# reefpi_pico_analog_out.net
KiCad netlist of a schematic drawn in Altium Designer
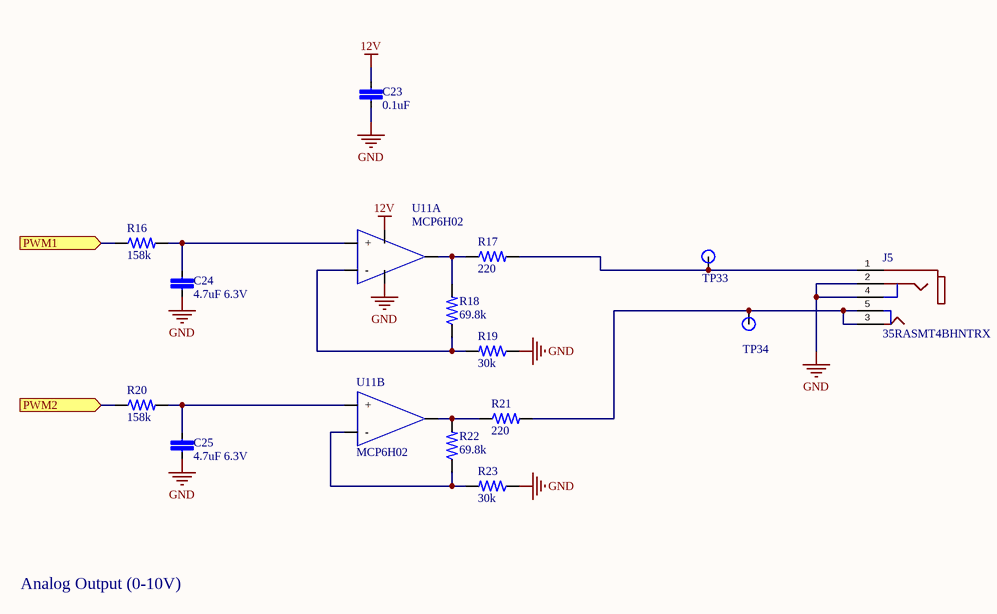
[diagram p0: reefpi_pico_analog_out.SchDoc]

(export (version "E")
  (design (tool "Eeschema 10.0.6"))
  (components
    (comp (ref "C23") (value "0.1uF") (footprint "C0603") (libsource (lib "rcl") (part "C-EU")))
    (comp (ref "C24") (value "4.7uF 6.3V") (footprint "C0603") (libsource (lib "rcl") (part "C-EU")))
    (comp (ref "C25") (value "4.7uF 6.3V") (footprint "C0603") (libsource (lib "rcl") (part "C-EU")))
    (comp (ref "J5")
      (value "35RASMT4BHNTRX")
      (footprint "35RASMT4BHNTRX")
      (libsource (lib "connectors") (part "35RASMT4BHNTRX"))
    )
    (comp (ref "R16") (value "158k") (footprint "R0603") (libsource (lib "rcl") (part "R-US")))
    (comp (ref "R17") (value "220") (footprint "R0603") (libsource (lib "rcl") (part "R-US")))
    (comp (ref "R18") (value "69.8k") (footprint "R0603") (libsource (lib "rcl") (part "R-US")))
    (comp (ref "R19") (value "30k") (footprint "R0603") (libsource (lib "rcl") (part "R-US")))
    (comp (ref "R20") (value "158k") (footprint "R0603") (libsource (lib "rcl") (part "R-US")))
    (comp (ref "R21") (value "220") (footprint "R0603") (libsource (lib "rcl") (part "R-US")))
    (comp (ref "R22") (value "69.8k") (footprint "R0603") (libsource (lib "rcl") (part "R-US")))
    (comp (ref "R23") (value "30k") (footprint "R0603") (libsource (lib "rcl") (part "R-US")))
    (comp (ref "TP33") (value "TP") (footprint "TP_0.89mm") (libsource (lib "testpoints") (part "TP")))
    (comp (ref "TP34") (value "TP") (footprint "TP_0.89mm") (libsource (lib "testpoints") (part "TP")))
    (comp (ref "U11") (value "MCP6H02") (footprint "SO-08") (libsource (lib "microchip") (part "MCP6H02")))
  )
  (nets
    (net (code "1") (name "/PWM1") (class "Default")
      (node (ref "R16") (pin "1") (pinfunction "1_1") (pintype "passive"))
    )
    (net (code "2") (name "/PWM2") (class "Default")
      (node (ref "R20") (pin "1") (pinfunction "1_1") (pintype "passive"))
    )
    (net (code "3") (name "12V") (class "Default")
      (node (ref "C23") (pin "1") (pinfunction "1_1") (pintype "passive"))
      (node (ref "U11") (pin "8") (pinfunction "Vdd_8") (pintype "power_in"))
    )
    (net (code "4") (name "GND") (class "Default")
      (node (ref "C23") (pin "2") (pinfunction "2_2") (pintype "passive"))
      (node (ref "C24") (pin "2") (pinfunction "2_2") (pintype "passive"))
      (node (ref "C25") (pin "2") (pinfunction "2_2") (pintype "passive"))
      (node (ref "J5") (pin "2") (pinfunction "MID_2") (pintype "passive"))
      (node (ref "J5") (pin "4") (pinfunction "MID_4") (pintype "passive"))
      (node (ref "R19") (pin "1") (pinfunction "1_1") (pintype "passive"))
      (node (ref "R23") (pin "1") (pinfunction "1_1") (pintype "passive"))
      (node (ref "U11") (pin "4") (pinfunction "GND_4") (pintype "power_in"))
    )
    (net (code "5") (name "Net-(J5-OUTER)") (class "Default")
      (node (ref "J5") (pin "1") (pinfunction "OUTER_1") (pintype "passive"))
      (node (ref "R17") (pin "2") (pinfunction "2_2") (pintype "passive"))
      (node (ref "TP33") (pin "1") (pinfunction "1_1") (pintype "passive"))
    )
    (net (code "6") (name "Net-(J5-TIP)") (class "Default")
      (node (ref "J5") (pin "3") (pinfunction "TIP_3") (pintype "passive"))
      (node (ref "J5") (pin "5") (pinfunction "MID_5") (pintype "passive"))
      (node (ref "R21") (pin "2") (pinfunction "2_2") (pintype "passive"))
      (node (ref "TP34") (pin "1") (pinfunction "1_1") (pintype "passive"))
    )
    (net (code "7") (name "Net-(U11A-+)") (class "Default")
      (node (ref "C24") (pin "1") (pinfunction "1_1") (pintype "passive"))
      (node (ref "R16") (pin "2") (pinfunction "2_2") (pintype "passive"))
      (node (ref "U11") (pin "3") (pinfunction "+_3") (pintype "passive"))
    )
    (net (code "8") (name "Net-(U11A--)") (class "Default")
      (node (ref "R18") (pin "1") (pinfunction "1_1") (pintype "passive"))
      (node (ref "R19") (pin "2") (pinfunction "2_2") (pintype "passive"))
      (node (ref "U11") (pin "2") (pinfunction "-_2") (pintype "passive"))
    )
    (net (code "9") (name "Net-(U11A-OUTA)") (class "Default")
      (node (ref "R17") (pin "1") (pinfunction "1_1") (pintype "passive"))
      (node (ref "R18") (pin "2") (pinfunction "2_2") (pintype "passive"))
      (node (ref "U11") (pin "1") (pinfunction "OUTA_1") (pintype "passive"))
    )
    (net (code "10") (name "Net-(U11B-+)") (class "Default")
      (node (ref "C25") (pin "1") (pinfunction "1_1") (pintype "passive"))
      (node (ref "R20") (pin "2") (pinfunction "2_2") (pintype "passive"))
      (node (ref "U11") (pin "5") (pinfunction "+_5") (pintype "passive"))
    )
    (net (code "11") (name "Net-(U11B--)") (class "Default")
      (node (ref "R22") (pin "1") (pinfunction "1_1") (pintype "passive"))
      (node (ref "R23") (pin "2") (pinfunction "2_2") (pintype "passive"))
      (node (ref "U11") (pin "6") (pinfunction "-_6") (pintype "passive"))
    )
    (net (code "12") (name "Net-(U11B-OUTB)") (class "Default")
      (node (ref "R21") (pin "1") (pinfunction "1_1") (pintype "passive"))
      (node (ref "R22") (pin "2") (pinfunction "2_2") (pintype "passive"))
      (node (ref "U11") (pin "7") (pinfunction "OUTB_7") (pintype "passive"))
    )
  )
)
